# light-ring.net
KiCad netlist of a schematic drawn in EAGLE
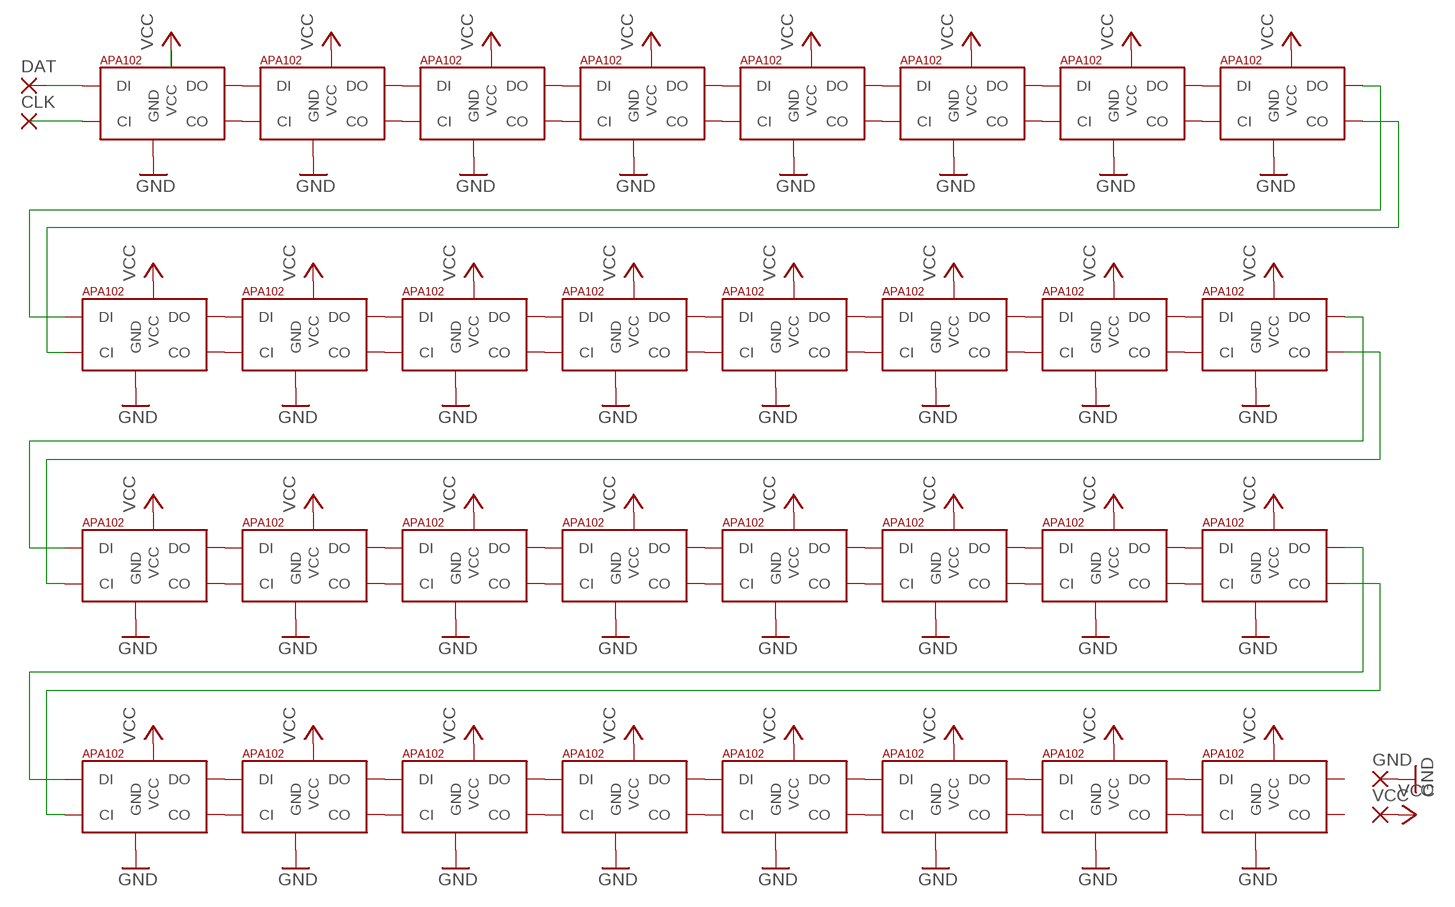
[diagram p0: schematic, sheet 1]

(export (version "E")
  (design (tool "Eeschema 10.0.6"))
  (components
    (comp (ref "CLK")
      (value "2,15/1,0")
      (footprint "eagle-import:2,15_1,0")
      (libsource (lib "eagle-import") (part "2,15/1,0"))
    )
    (comp (ref "DAT")
      (value "2,15/1,0")
      (footprint "eagle-import:2,15_1,0")
      (libsource (lib "eagle-import") (part "2,15/1,0"))
    )
    (comp (ref "GND")
      (value "2,15/1,0")
      (footprint "eagle-import:2,15_1,0")
      (libsource (lib "eagle-import") (part "2,15/1,0"))
    )
    (comp (ref "LED_1")
      (value "APA1025050")
      (footprint "eagle-import:APA102_5050")
      (libsource (lib "eagle-import") (part "APA1025050"))
    )
    (comp (ref "LED_2")
      (value "APA1025050")
      (footprint "eagle-import:APA102_5050")
      (libsource (lib "eagle-import") (part "APA1025050"))
    )
    (comp (ref "LED_3")
      (value "APA1025050")
      (footprint "eagle-import:APA102_5050")
      (libsource (lib "eagle-import") (part "APA1025050"))
    )
    (comp (ref "LED_4")
      (value "APA1025050")
      (footprint "eagle-import:APA102_5050")
      (libsource (lib "eagle-import") (part "APA1025050"))
    )
    (comp (ref "LED_5")
      (value "APA1025050")
      (footprint "eagle-import:APA102_5050")
      (libsource (lib "eagle-import") (part "APA1025050"))
    )
    (comp (ref "LED_6")
      (value "APA1025050")
      (footprint "eagle-import:APA102_5050")
      (libsource (lib "eagle-import") (part "APA1025050"))
    )
    (comp (ref "LED_7")
      (value "APA1025050")
      (footprint "eagle-import:APA102_5050")
      (libsource (lib "eagle-import") (part "APA1025050"))
    )
    (comp (ref "LED_8")
      (value "APA1025050")
      (footprint "eagle-import:APA102_5050")
      (libsource (lib "eagle-import") (part "APA1025050"))
    )
    (comp (ref "LED_9")
      (value "APA1025050")
      (footprint "eagle-import:APA102_5050")
      (libsource (lib "eagle-import") (part "APA1025050"))
    )
    (comp (ref "LED_10")
      (value "APA1025050")
      (footprint "eagle-import:APA102_5050")
      (libsource (lib "eagle-import") (part "APA1025050"))
    )
    (comp (ref "LED_11")
      (value "APA1025050")
      (footprint "eagle-import:APA102_5050")
      (libsource (lib "eagle-import") (part "APA1025050"))
    )
    (comp (ref "LED_12")
      (value "APA1025050")
      (footprint "eagle-import:APA102_5050")
      (libsource (lib "eagle-import") (part "APA1025050"))
    )
    (comp (ref "LED_13")
      (value "APA1025050")
      (footprint "eagle-import:APA102_5050")
      (libsource (lib "eagle-import") (part "APA1025050"))
    )
    (comp (ref "LED_14")
      (value "APA1025050")
      (footprint "eagle-import:APA102_5050")
      (libsource (lib "eagle-import") (part "APA1025050"))
    )
    (comp (ref "LED_15")
      (value "APA1025050")
      (footprint "eagle-import:APA102_5050")
      (libsource (lib "eagle-import") (part "APA1025050"))
    )
    (comp (ref "LED_16")
      (value "APA1025050")
      (footprint "eagle-import:APA102_5050")
      (libsource (lib "eagle-import") (part "APA1025050"))
    )
    (comp (ref "LED_17")
      (value "APA1025050")
      (footprint "eagle-import:APA102_5050")
      (libsource (lib "eagle-import") (part "APA1025050"))
    )
    (comp (ref "LED_18")
      (value "APA1025050")
      (footprint "eagle-import:APA102_5050")
      (libsource (lib "eagle-import") (part "APA1025050"))
    )
    (comp (ref "LED_19")
      (value "APA1025050")
      (footprint "eagle-import:APA102_5050")
      (libsource (lib "eagle-import") (part "APA1025050"))
    )
    (comp (ref "LED_20")
      (value "APA1025050")
      (footprint "eagle-import:APA102_5050")
      (libsource (lib "eagle-import") (part "APA1025050"))
    )
    (comp (ref "LED_21")
      (value "APA1025050")
      (footprint "eagle-import:APA102_5050")
      (libsource (lib "eagle-import") (part "APA1025050"))
    )
    (comp (ref "LED_22")
      (value "APA1025050")
      (footprint "eagle-import:APA102_5050")
      (libsource (lib "eagle-import") (part "APA1025050"))
    )
    (comp (ref "LED_23")
      (value "APA1025050")
      (footprint "eagle-import:APA102_5050")
      (libsource (lib "eagle-import") (part "APA1025050"))
    )
    (comp (ref "LED_24")
      (value "APA1025050")
      (footprint "eagle-import:APA102_5050")
      (libsource (lib "eagle-import") (part "APA1025050"))
    )
    (comp (ref "LED_25")
      (value "APA1025050")
      (footprint "eagle-import:APA102_5050")
      (libsource (lib "eagle-import") (part "APA1025050"))
    )
    (comp (ref "LED_26")
      (value "APA1025050")
      (footprint "eagle-import:APA102_5050")
      (libsource (lib "eagle-import") (part "APA1025050"))
    )
    (comp (ref "LED_27")
      (value "APA1025050")
      (footprint "eagle-import:APA102_5050")
      (libsource (lib "eagle-import") (part "APA1025050"))
    )
    (comp (ref "LED_28")
      (value "APA1025050")
      (footprint "eagle-import:APA102_5050")
      (libsource (lib "eagle-import") (part "APA1025050"))
    )
    (comp (ref "LED_29")
      (value "APA1025050")
      (footprint "eagle-import:APA102_5050")
      (libsource (lib "eagle-import") (part "APA1025050"))
    )
    (comp (ref "LED_30")
      (value "APA1025050")
      (footprint "eagle-import:APA102_5050")
      (libsource (lib "eagle-import") (part "APA1025050"))
    )
    (comp (ref "LED_31")
      (value "APA1025050")
      (footprint "eagle-import:APA102_5050")
      (libsource (lib "eagle-import") (part "APA1025050"))
    )
    (comp (ref "LED_32")
      (value "APA1025050")
      (footprint "eagle-import:APA102_5050")
      (libsource (lib "eagle-import") (part "APA1025050"))
    )
    (comp (ref "VCC")
      (value "2,15/1,0")
      (footprint "eagle-import:2,15_1,0")
      (libsource (lib "eagle-import") (part "2,15/1,0"))
    )
  )
  (nets
    (net (code "1") (name "GND") (class "Default")
      (node (ref "GND") (pin "1") (pinfunction "P_1") (pintype "passive"))
      (node (ref "LED_1") (pin "6") (pinfunction "GND_6") (pintype "bidirectional"))
      (node (ref "LED_10") (pin "6") (pinfunction "GND_6") (pintype "bidirectional"))
      (node (ref "LED_11") (pin "6") (pinfunction "GND_6") (pintype "bidirectional"))
      (node (ref "LED_12") (pin "6") (pinfunction "GND_6") (pintype "bidirectional"))
      (node (ref "LED_13") (pin "6") (pinfunction "GND_6") (pintype "bidirectional"))
      (node (ref "LED_14") (pin "6") (pinfunction "GND_6") (pintype "bidirectional"))
      (node (ref "LED_15") (pin "6") (pinfunction "GND_6") (pintype "bidirectional"))
      (node (ref "LED_16") (pin "6") (pinfunction "GND_6") (pintype "bidirectional"))
      (node (ref "LED_17") (pin "6") (pinfunction "GND_6") (pintype "bidirectional"))
      (node (ref "LED_18") (pin "6") (pinfunction "GND_6") (pintype "bidirectional"))
      (node (ref "LED_19") (pin "6") (pinfunction "GND_6") (pintype "bidirectional"))
      (node (ref "LED_2") (pin "6") (pinfunction "GND_6") (pintype "bidirectional"))
      (node (ref "LED_20") (pin "6") (pinfunction "GND_6") (pintype "bidirectional"))
      (node (ref "LED_21") (pin "6") (pinfunction "GND_6") (pintype "bidirectional"))
      (node (ref "LED_22") (pin "6") (pinfunction "GND_6") (pintype "bidirectional"))
      (node (ref "LED_23") (pin "6") (pinfunction "GND_6") (pintype "bidirectional"))
      (node (ref "LED_24") (pin "6") (pinfunction "GND_6") (pintype "bidirectional"))
      (node (ref "LED_25") (pin "6") (pinfunction "GND_6") (pintype "bidirectional"))
      (node (ref "LED_26") (pin "6") (pinfunction "GND_6") (pintype "bidirectional"))
      (node (ref "LED_27") (pin "6") (pinfunction "GND_6") (pintype "bidirectional"))
      (node (ref "LED_28") (pin "6") (pinfunction "GND_6") (pintype "bidirectional"))
      (node (ref "LED_29") (pin "6") (pinfunction "GND_6") (pintype "bidirectional"))
      (node (ref "LED_3") (pin "6") (pinfunction "GND_6") (pintype "bidirectional"))
      (node (ref "LED_30") (pin "6") (pinfunction "GND_6") (pintype "bidirectional"))
      (node (ref "LED_31") (pin "6") (pinfunction "GND_6") (pintype "bidirectional"))
      (node (ref "LED_32") (pin "6") (pinfunction "GND_6") (pintype "bidirectional"))
      (node (ref "LED_4") (pin "6") (pinfunction "GND_6") (pintype "bidirectional"))
      (node (ref "LED_5") (pin "6") (pinfunction "GND_6") (pintype "bidirectional"))
      (node (ref "LED_6") (pin "6") (pinfunction "GND_6") (pintype "bidirectional"))
      (node (ref "LED_7") (pin "6") (pinfunction "GND_6") (pintype "bidirectional"))
      (node (ref "LED_8") (pin "6") (pinfunction "GND_6") (pintype "bidirectional"))
      (node (ref "LED_9") (pin "6") (pinfunction "GND_6") (pintype "bidirectional"))
    )
    (net (code "2") (name "Net-(CLK-P)") (class "Default")
      (node (ref "CLK") (pin "1") (pinfunction "P_1") (pintype "passive"))
      (node (ref "LED_1") (pin "5") (pinfunction "CI_5") (pintype "bidirectional"))
    )
    (net (code "3") (name "Net-(DAT-P)") (class "Default")
      (node (ref "DAT") (pin "1") (pinfunction "P_1") (pintype "passive"))
      (node (ref "LED_1") (pin "4") (pinfunction "DI_4") (pintype "bidirectional"))
    )
    (net (code "4") (name "Net-(LED_1-CO)") (class "Default")
      (node (ref "LED_1") (pin "2") (pinfunction "CO_2") (pintype "bidirectional"))
      (node (ref "LED_2") (pin "5") (pinfunction "CI_5") (pintype "bidirectional"))
    )
    (net (code "5") (name "Net-(LED_1-DO)") (class "Default")
      (node (ref "LED_1") (pin "3") (pinfunction "DO_3") (pintype "bidirectional"))
      (node (ref "LED_2") (pin "4") (pinfunction "DI_4") (pintype "bidirectional"))
    )
    (net (code "6") (name "Net-(LED_2-CO)") (class "Default")
      (node (ref "LED_2") (pin "2") (pinfunction "CO_2") (pintype "bidirectional"))
      (node (ref "LED_3") (pin "5") (pinfunction "CI_5") (pintype "bidirectional"))
    )
    (net (code "7") (name "Net-(LED_2-DO)") (class "Default")
      (node (ref "LED_2") (pin "3") (pinfunction "DO_3") (pintype "bidirectional"))
      (node (ref "LED_3") (pin "4") (pinfunction "DI_4") (pintype "bidirectional"))
    )
    (net (code "8") (name "Net-(LED_3-CO)") (class "Default")
      (node (ref "LED_3") (pin "2") (pinfunction "CO_2") (pintype "bidirectional"))
      (node (ref "LED_4") (pin "5") (pinfunction "CI_5") (pintype "bidirectional"))
    )
    (net (code "9") (name "Net-(LED_3-DO)") (class "Default")
      (node (ref "LED_3") (pin "3") (pinfunction "DO_3") (pintype "bidirectional"))
      (node (ref "LED_4") (pin "4") (pinfunction "DI_4") (pintype "bidirectional"))
    )
    (net (code "10") (name "Net-(LED_4-CO)") (class "Default")
      (node (ref "LED_4") (pin "2") (pinfunction "CO_2") (pintype "bidirectional"))
      (node (ref "LED_5") (pin "5") (pinfunction "CI_5") (pintype "bidirectional"))
    )
    (net (code "11") (name "Net-(LED_4-DO)") (class "Default")
      (node (ref "LED_4") (pin "3") (pinfunction "DO_3") (pintype "bidirectional"))
      (node (ref "LED_5") (pin "4") (pinfunction "DI_4") (pintype "bidirectional"))
    )
    (net (code "12") (name "Net-(LED_5-CO)") (class "Default")
      (node (ref "LED_5") (pin "2") (pinfunction "CO_2") (pintype "bidirectional"))
      (node (ref "LED_6") (pin "5") (pinfunction "CI_5") (pintype "bidirectional"))
    )
    (net (code "13") (name "Net-(LED_5-DO)") (class "Default")
      (node (ref "LED_5") (pin "3") (pinfunction "DO_3") (pintype "bidirectional"))
      (node (ref "LED_6") (pin "4") (pinfunction "DI_4") (pintype "bidirectional"))
    )
    (net (code "14") (name "Net-(LED_6-CO)") (class "Default")
      (node (ref "LED_6") (pin "2") (pinfunction "CO_2") (pintype "bidirectional"))
      (node (ref "LED_7") (pin "5") (pinfunction "CI_5") (pintype "bidirectional"))
    )
    (net (code "15") (name "Net-(LED_6-DO)") (class "Default")
      (node (ref "LED_6") (pin "3") (pinfunction "DO_3") (pintype "bidirectional"))
      (node (ref "LED_7") (pin "4") (pinfunction "DI_4") (pintype "bidirectional"))
    )
    (net (code "16") (name "Net-(LED_7-CO)") (class "Default")
      (node (ref "LED_7") (pin "2") (pinfunction "CO_2") (pintype "bidirectional"))
      (node (ref "LED_8") (pin "5") (pinfunction "CI_5") (pintype "bidirectional"))
    )
    (net (code "17") (name "Net-(LED_7-DO)") (class "Default")
      (node (ref "LED_7") (pin "3") (pinfunction "DO_3") (pintype "bidirectional"))
      (node (ref "LED_8") (pin "4") (pinfunction "DI_4") (pintype "bidirectional"))
    )
    (net (code "18") (name "Net-(LED_8-CO)") (class "Default")
      (node (ref "LED_8") (pin "2") (pinfunction "CO_2") (pintype "bidirectional"))
      (node (ref "LED_9") (pin "5") (pinfunction "CI_5") (pintype "bidirectional"))
    )
    (net (code "19") (name "Net-(LED_8-DO)") (class "Default")
      (node (ref "LED_8") (pin "3") (pinfunction "DO_3") (pintype "bidirectional"))
      (node (ref "LED_9") (pin "4") (pinfunction "DI_4") (pintype "bidirectional"))
    )
    (net (code "20") (name "Net-(LED_10-CI)") (class "Default")
      (node (ref "LED_10") (pin "5") (pinfunction "CI_5") (pintype "bidirectional"))
      (node (ref "LED_9") (pin "2") (pinfunction "CO_2") (pintype "bidirectional"))
    )
    (net (code "21") (name "Net-(LED_10-CO)") (class "Default")
      (node (ref "LED_10") (pin "2") (pinfunction "CO_2") (pintype "bidirectional"))
      (node (ref "LED_11") (pin "5") (pinfunction "CI_5") (pintype "bidirectional"))
    )
    (net (code "22") (name "Net-(LED_10-DI)") (class "Default")
      (node (ref "LED_10") (pin "4") (pinfunction "DI_4") (pintype "bidirectional"))
      (node (ref "LED_9") (pin "3") (pinfunction "DO_3") (pintype "bidirectional"))
    )
    (net (code "23") (name "Net-(LED_10-DO)") (class "Default")
      (node (ref "LED_10") (pin "3") (pinfunction "DO_3") (pintype "bidirectional"))
      (node (ref "LED_11") (pin "4") (pinfunction "DI_4") (pintype "bidirectional"))
    )
    (net (code "24") (name "Net-(LED_11-CO)") (class "Default")
      (node (ref "LED_11") (pin "2") (pinfunction "CO_2") (pintype "bidirectional"))
      (node (ref "LED_12") (pin "5") (pinfunction "CI_5") (pintype "bidirectional"))
    )
    (net (code "25") (name "Net-(LED_11-DO)") (class "Default")
      (node (ref "LED_11") (pin "3") (pinfunction "DO_3") (pintype "bidirectional"))
      (node (ref "LED_12") (pin "4") (pinfunction "DI_4") (pintype "bidirectional"))
    )
    (net (code "26") (name "Net-(LED_12-CO)") (class "Default")
      (node (ref "LED_12") (pin "2") (pinfunction "CO_2") (pintype "bidirectional"))
      (node (ref "LED_13") (pin "5") (pinfunction "CI_5") (pintype "bidirectional"))
    )
    (net (code "27") (name "Net-(LED_12-DO)") (class "Default")
      (node (ref "LED_12") (pin "3") (pinfunction "DO_3") (pintype "bidirectional"))
      (node (ref "LED_13") (pin "4") (pinfunction "DI_4") (pintype "bidirectional"))
    )
    (net (code "28") (name "Net-(LED_13-CO)") (class "Default")
      (node (ref "LED_13") (pin "2") (pinfunction "CO_2") (pintype "bidirectional"))
      (node (ref "LED_14") (pin "5") (pinfunction "CI_5") (pintype "bidirectional"))
    )
    (net (code "29") (name "Net-(LED_13-DO)") (class "Default")
      (node (ref "LED_13") (pin "3") (pinfunction "DO_3") (pintype "bidirectional"))
      (node (ref "LED_14") (pin "4") (pinfunction "DI_4") (pintype "bidirectional"))
    )
    (net (code "30") (name "Net-(LED_14-CO)") (class "Default")
      (node (ref "LED_14") (pin "2") (pinfunction "CO_2") (pintype "bidirectional"))
      (node (ref "LED_15") (pin "5") (pinfunction "CI_5") (pintype "bidirectional"))
    )
    (net (code "31") (name "Net-(LED_14-DO)") (class "Default")
      (node (ref "LED_14") (pin "3") (pinfunction "DO_3") (pintype "bidirectional"))
      (node (ref "LED_15") (pin "4") (pinfunction "DI_4") (pintype "bidirectional"))
    )
    (net (code "32") (name "Net-(LED_15-CO)") (class "Default")
      (node (ref "LED_15") (pin "2") (pinfunction "CO_2") (pintype "bidirectional"))
      (node (ref "LED_16") (pin "5") (pinfunction "CI_5") (pintype "bidirectional"))
    )
    (net (code "33") (name "Net-(LED_15-DO)") (class "Default")
      (node (ref "LED_15") (pin "3") (pinfunction "DO_3") (pintype "bidirectional"))
      (node (ref "LED_16") (pin "4") (pinfunction "DI_4") (pintype "bidirectional"))
    )
    (net (code "34") (name "Net-(LED_16-CO)") (class "Default")
      (node (ref "LED_16") (pin "2") (pinfunction "CO_2") (pintype "bidirectional"))
      (node (ref "LED_17") (pin "5") (pinfunction "CI_5") (pintype "bidirectional"))
    )
    (net (code "35") (name "Net-(LED_16-DO)") (class "Default")
      (node (ref "LED_16") (pin "3") (pinfunction "DO_3") (pintype "bidirectional"))
      (node (ref "LED_17") (pin "4") (pinfunction "DI_4") (pintype "bidirectional"))
    )
    (net (code "36") (name "Net-(LED_17-CO)") (class "Default")
      (node (ref "LED_17") (pin "2") (pinfunction "CO_2") (pintype "bidirectional"))
      (node (ref "LED_18") (pin "5") (pinfunction "CI_5") (pintype "bidirectional"))
    )
    (net (code "37") (name "Net-(LED_17-DO)") (class "Default")
      (node (ref "LED_17") (pin "3") (pinfunction "DO_3") (pintype "bidirectional"))
      (node (ref "LED_18") (pin "4") (pinfunction "DI_4") (pintype "bidirectional"))
    )
    (net (code "38") (name "Net-(LED_18-CO)") (class "Default")
      (node (ref "LED_18") (pin "2") (pinfunction "CO_2") (pintype "bidirectional"))
      (node (ref "LED_19") (pin "5") (pinfunction "CI_5") (pintype "bidirectional"))
    )
    (net (code "39") (name "Net-(LED_18-DO)") (class "Default")
      (node (ref "LED_18") (pin "3") (pinfunction "DO_3") (pintype "bidirectional"))
      (node (ref "LED_19") (pin "4") (pinfunction "DI_4") (pintype "bidirectional"))
    )
    (net (code "40") (name "Net-(LED_19-CO)") (class "Default")
      (node (ref "LED_19") (pin "2") (pinfunction "CO_2") (pintype "bidirectional"))
      (node (ref "LED_20") (pin "5") (pinfunction "CI_5") (pintype "bidirectional"))
    )
    (net (code "41") (name "Net-(LED_19-DO)") (class "Default")
      (node (ref "LED_19") (pin "3") (pinfunction "DO_3") (pintype "bidirectional"))
      (node (ref "LED_20") (pin "4") (pinfunction "DI_4") (pintype "bidirectional"))
    )
    (net (code "42") (name "Net-(LED_20-CO)") (class "Default")
      (node (ref "LED_20") (pin "2") (pinfunction "CO_2") (pintype "bidirectional"))
      (node (ref "LED_21") (pin "5") (pinfunction "CI_5") (pintype "bidirectional"))
    )
    (net (code "43") (name "Net-(LED_20-DO)") (class "Default")
      (node (ref "LED_20") (pin "3") (pinfunction "DO_3") (pintype "bidirectional"))
      (node (ref "LED_21") (pin "4") (pinfunction "DI_4") (pintype "bidirectional"))
    )
    (net (code "44") (name "Net-(LED_21-CO)") (class "Default")
      (node (ref "LED_21") (pin "2") (pinfunction "CO_2") (pintype "bidirectional"))
      (node (ref "LED_22") (pin "5") (pinfunction "CI_5") (pintype "bidirectional"))
    )
    (net (code "45") (name "Net-(LED_21-DO)") (class "Default")
      (node (ref "LED_21") (pin "3") (pinfunction "DO_3") (pintype "bidirectional"))
      (node (ref "LED_22") (pin "4") (pinfunction "DI_4") (pintype "bidirectional"))
    )
    (net (code "46") (name "Net-(LED_22-CO)") (class "Default")
      (node (ref "LED_22") (pin "2") (pinfunction "CO_2") (pintype "bidirectional"))
      (node (ref "LED_23") (pin "5") (pinfunction "CI_5") (pintype "bidirectional"))
    )
    (net (code "47") (name "Net-(LED_22-DO)") (class "Default")
      (node (ref "LED_22") (pin "3") (pinfunction "DO_3") (pintype "bidirectional"))
      (node (ref "LED_23") (pin "4") (pinfunction "DI_4") (pintype "bidirectional"))
    )
    (net (code "48") (name "Net-(LED_23-CO)") (class "Default")
      (node (ref "LED_23") (pin "2") (pinfunction "CO_2") (pintype "bidirectional"))
      (node (ref "LED_24") (pin "5") (pinfunction "CI_5") (pintype "bidirectional"))
    )
    (net (code "49") (name "Net-(LED_23-DO)") (class "Default")
      (node (ref "LED_23") (pin "3") (pinfunction "DO_3") (pintype "bidirectional"))
      (node (ref "LED_24") (pin "4") (pinfunction "DI_4") (pintype "bidirectional"))
    )
    (net (code "50") (name "Net-(LED_24-CO)") (class "Default")
      (node (ref "LED_24") (pin "2") (pinfunction "CO_2") (pintype "bidirectional"))
      (node (ref "LED_25") (pin "5") (pinfunction "CI_5") (pintype "bidirectional"))
    )
    (net (code "51") (name "Net-(LED_24-DO)") (class "Default")
      (node (ref "LED_24") (pin "3") (pinfunction "DO_3") (pintype "bidirectional"))
      (node (ref "LED_25") (pin "4") (pinfunction "DI_4") (pintype "bidirectional"))
    )
    (net (code "52") (name "Net-(LED_25-CO)") (class "Default")
      (node (ref "LED_25") (pin "2") (pinfunction "CO_2") (pintype "bidirectional"))
      (node (ref "LED_26") (pin "5") (pinfunction "CI_5") (pintype "bidirectional"))
    )
    (net (code "53") (name "Net-(LED_25-DO)") (class "Default")
      (node (ref "LED_25") (pin "3") (pinfunction "DO_3") (pintype "bidirectional"))
      (node (ref "LED_26") (pin "4") (pinfunction "DI_4") (pintype "bidirectional"))
    )
    (net (code "54") (name "Net-(LED_26-CO)") (class "Default")
      (node (ref "LED_26") (pin "2") (pinfunction "CO_2") (pintype "bidirectional"))
      (node (ref "LED_27") (pin "5") (pinfunction "CI_5") (pintype "bidirectional"))
    )
    (net (code "55") (name "Net-(LED_26-DO)") (class "Default")
      (node (ref "LED_26") (pin "3") (pinfunction "DO_3") (pintype "bidirectional"))
      (node (ref "LED_27") (pin "4") (pinfunction "DI_4") (pintype "bidirectional"))
    )
    (net (code "56") (name "Net-(LED_27-CO)") (class "Default")
      (node (ref "LED_27") (pin "2") (pinfunction "CO_2") (pintype "bidirectional"))
      (node (ref "LED_28") (pin "5") (pinfunction "CI_5") (pintype "bidirectional"))
    )
    (net (code "57") (name "Net-(LED_27-DO)") (class "Default")
      (node (ref "LED_27") (pin "3") (pinfunction "DO_3") (pintype "bidirectional"))
      (node (ref "LED_28") (pin "4") (pinfunction "DI_4") (pintype "bidirectional"))
    )
    (net (code "58") (name "Net-(LED_28-CO)") (class "Default")
      (node (ref "LED_28") (pin "2") (pinfunction "CO_2") (pintype "bidirectional"))
      (node (ref "LED_29") (pin "5") (pinfunction "CI_5") (pintype "bidirectional"))
    )
    (net (code "59") (name "Net-(LED_28-DO)") (class "Default")
      (node (ref "LED_28") (pin "3") (pinfunction "DO_3") (pintype "bidirectional"))
      (node (ref "LED_29") (pin "4") (pinfunction "DI_4") (pintype "bidirectional"))
    )
    (net (code "60") (name "Net-(LED_29-CO)") (class "Default")
      (node (ref "LED_29") (pin "2") (pinfunction "CO_2") (pintype "bidirectional"))
      (node (ref "LED_30") (pin "5") (pinfunction "CI_5") (pintype "bidirectional"))
    )
    (net (code "61") (name "Net-(LED_29-DO)") (class "Default")
      (node (ref "LED_29") (pin "3") (pinfunction "DO_3") (pintype "bidirectional"))
      (node (ref "LED_30") (pin "4") (pinfunction "DI_4") (pintype "bidirectional"))
    )
    (net (code "62") (name "Net-(LED_30-CO)") (class "Default")
      (node (ref "LED_30") (pin "2") (pinfunction "CO_2") (pintype "bidirectional"))
      (node (ref "LED_31") (pin "5") (pinfunction "CI_5") (pintype "bidirectional"))
    )
    (net (code "63") (name "Net-(LED_30-DO)") (class "Default")
      (node (ref "LED_30") (pin "3") (pinfunction "DO_3") (pintype "bidirectional"))
      (node (ref "LED_31") (pin "4") (pinfunction "DI_4") (pintype "bidirectional"))
    )
    (net (code "64") (name "Net-(LED_31-CO)") (class "Default")
      (node (ref "LED_31") (pin "2") (pinfunction "CO_2") (pintype "bidirectional"))
      (node (ref "LED_32") (pin "5") (pinfunction "CI_5") (pintype "bidirectional"))
    )
    (net (code "65") (name "Net-(LED_31-DO)") (class "Default")
      (node (ref "LED_31") (pin "3") (pinfunction "DO_3") (pintype "bidirectional"))
      (node (ref "LED_32") (pin "4") (pinfunction "DI_4") (pintype "bidirectional"))
    )
    (net (code "66") (name "VCC") (class "Default")
      (node (ref "LED_1") (pin "1") (pinfunction "VCC_1") (pintype "bidirectional"))
      (node (ref "LED_10") (pin "1") (pinfunction "VCC_1") (pintype "bidirectional"))
      (node (ref "LED_11") (pin "1") (pinfunction "VCC_1") (pintype "bidirectional"))
      (node (ref "LED_12") (pin "1") (pinfunction "VCC_1") (pintype "bidirectional"))
      (node (ref "LED_13") (pin "1") (pinfunction "VCC_1") (pintype "bidirectional"))
      (node (ref "LED_14") (pin "1") (pinfunction "VCC_1") (pintype "bidirectional"))
      (node (ref "LED_15") (pin "1") (pinfunction "VCC_1") (pintype "bidirectional"))
      (node (ref "LED_16") (pin "1") (pinfunction "VCC_1") (pintype "bidirectional"))
      (node (ref "LED_17") (pin "1") (pinfunction "VCC_1") (pintype "bidirectional"))
      (node (ref "LED_18") (pin "1") (pinfunction "VCC_1") (pintype "bidirectional"))
      (node (ref "LED_19") (pin "1") (pinfunction "VCC_1") (pintype "bidirectional"))
      (node (ref "LED_2") (pin "1") (pinfunction "VCC_1") (pintype "bidirectional"))
      (node (ref "LED_20") (pin "1") (pinfunction "VCC_1") (pintype "bidirectional"))
      (node (ref "LED_21") (pin "1") (pinfunction "VCC_1") (pintype "bidirectional"))
      (node (ref "LED_22") (pin "1") (pinfunction "VCC_1") (pintype "bidirectional"))
      (node (ref "LED_23") (pin "1") (pinfunction "VCC_1") (pintype "bidirectional"))
      (node (ref "LED_24") (pin "1") (pinfunction "VCC_1") (pintype "bidirectional"))
      (node (ref "LED_25") (pin "1") (pinfunction "VCC_1") (pintype "bidirectional"))
      (node (ref "LED_26") (pin "1") (pinfunction "VCC_1") (pintype "bidirectional"))
      (node (ref "LED_27") (pin "1") (pinfunction "VCC_1") (pintype "bidirectional"))
      (node (ref "LED_28") (pin "1") (pinfunction "VCC_1") (pintype "bidirectional"))
      (node (ref "LED_29") (pin "1") (pinfunction "VCC_1") (pintype "bidirectional"))
      (node (ref "LED_3") (pin "1") (pinfunction "VCC_1") (pintype "bidirectional"))
      (node (ref "LED_30") (pin "1") (pinfunction "VCC_1") (pintype "bidirectional"))
      (node (ref "LED_31") (pin "1") (pinfunction "VCC_1") (pintype "bidirectional"))
      (node (ref "LED_32") (pin "1") (pinfunction "VCC_1") (pintype "bidirectional"))
      (node (ref "LED_4") (pin "1") (pinfunction "VCC_1") (pintype "bidirectional"))
      (node (ref "LED_5") (pin "1") (pinfunction "VCC_1") (pintype "bidirectional"))
      (node (ref "LED_6") (pin "1") (pinfunction "VCC_1") (pintype "bidirectional"))
      (node (ref "LED_7") (pin "1") (pinfunction "VCC_1") (pintype "bidirectional"))
      (node (ref "LED_8") (pin "1") (pinfunction "VCC_1") (pintype "bidirectional"))
      (node (ref "LED_9") (pin "1") (pinfunction "VCC_1") (pintype "bidirectional"))
      (node (ref "VCC") (pin "1") (pinfunction "P_1") (pintype "passive"))
    )
    (net (code "67") (name "unconnected-(LED_32-CO-Pad2)") (class "Default")
      (node (ref "LED_32") (pin "2") (pinfunction "CO_2") (pintype "bidirectional"))
    )
    (net (code "68") (name "unconnected-(LED_32-DO-Pad3)") (class "Default")
      (node (ref "LED_32") (pin "3") (pinfunction "DO_3") (pintype "bidirectional"))
    )
  )
)
